# 5V_3V3_DIGITAL.net
KiCad netlist of a schematic drawn in Altium Designer
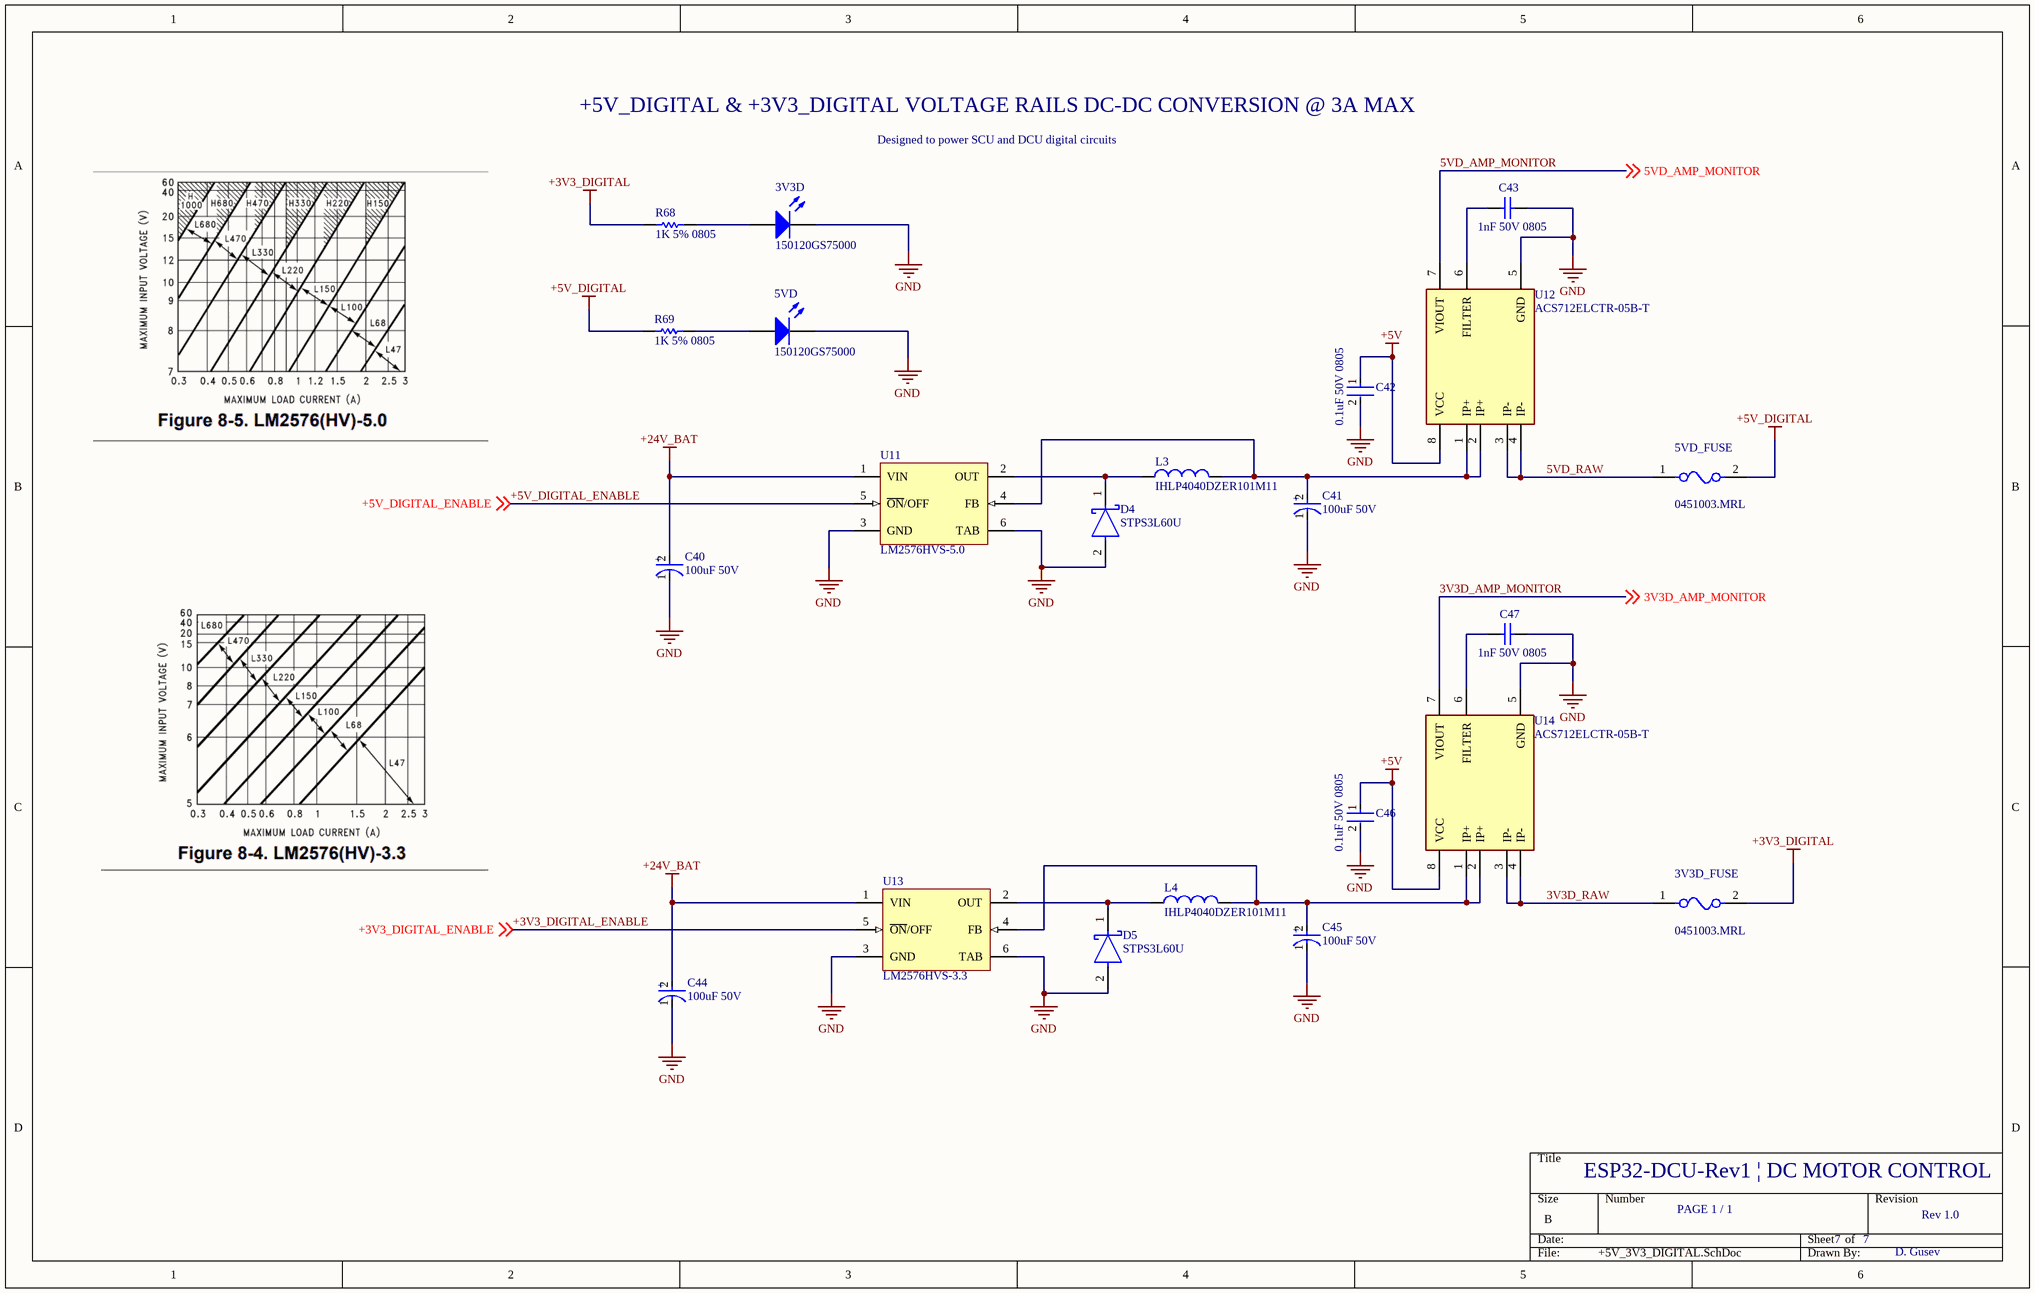
[diagram p0: +5V_3V3_DIGITAL.SchDoc]

(export (version "E")
  (design (tool "Eeschema 10.0.6"))
  (components
    (comp (ref "3V3D")
      (value "150120GS75000")
      (footprint "1206_A")
      (description "SMD mono-color Chip LED, WL-SMCW, Green")
      (fields (field (name "MANUFACTURER") "Wuerth Elektronik"))
      (libsource (lib "Altium Content Vault") (part "WE-LED_K1A2-2"))
    )
    (comp (ref "3V3D_FUSE")
      (value "0451003.MRL")
      (footprint "FP-0451-MFG")
      (description "FUSE BRD MNT 3A 125VAC/VDC 2SMD")
      (fields
        (field (name "MANUFACTURER") "Littelfuse Inc")
        (field (name "OCTOPART") "https://octopart.com/0451003.mrl-littelfuse-566380")
      )
      (libsource (lib "Altium Content Vault") (part "5bcf9b9f640e542cf0359d10258e979"))
    )
    (comp (ref "5VD")
      (value "150120GS75000")
      (footprint "1206_A")
      (description "SMD mono-color Chip LED, WL-SMCW, Green")
      (fields (field (name "MANUFACTURER") "Wuerth Elektronik"))
      (libsource (lib "Altium Content Vault") (part "WE-LED_K1A2-2"))
    )
    (comp (ref "5VD_FUSE")
      (value "0451003.MRL")
      (footprint "FP-0451-MFG")
      (description "FUSE BRD MNT 3A 125VAC/VDC 2SMD")
      (fields
        (field (name "MANUFACTURER") "Littelfuse Inc")
        (field (name "OCTOPART") "https://octopart.com/0451003.mrl-littelfuse-566380")
      )
      (libsource (lib "Altium Content Vault") (part "5bcf9b9f640e542cf0359d10258e979"))
    )
    (comp (ref "C40")
      (value "100uF 50V")
      (footprint "FP-EEE-FK1H101P-MFG")
      (description "CAP ALUM 100UF 20% 50V SMD")
      (fields (field (name "TOLERANCE") "20%") (field (name "MANUFACTURER PART NUMBER") "EEE-FK1H101P"))
      (libsource (lib "Altium Content Vault") (part "cf48714ba7e38822c1575c7ec0b6d1f"))
    )
    (comp (ref "C41")
      (value "100uF 50V")
      (footprint "FP-EEE-FK1H101P-MFG")
      (description "CAP ALUM 100UF 20% 50V SMD")
      (fields (field (name "TOLERANCE") "20%") (field (name "MANUFACTURER PART NUMBER") "EEE-FK1H101P"))
      (libsource (lib "Altium Content Vault") (part "cf48714ba7e38822c1575c7ec0b6d1f"))
    )
    (comp (ref "C42")
      (value "0.1uF 50V 0805")
      (footprint "FP-C0805C-DN-MFG")
      (description "CAP CER 0.1UF 50V X7R 0805")
      (fields
        (field (name "MANUFACTURER PART NUMBER") "C0805C104K5RACTU")
        (field (name "MANUFACTURER") "KEMET")
      )
      (libsource (lib "Altium Content Vault") (part "b4654b650e69147ec39a6b967a45e02"))
    )
    (comp (ref "C43")
      (value "1nF 50V 0805")
      (footprint "CAPC2013X94X50ML20T25")
      (fields
        (field (name "PART NUMBER") "08055C102KAT2A.")
        (field (name "MANUFACTURER") "AVX Interconnect / Elco")
      )
      (libsource (lib "Altium Content Vault") (part "CAP"))
    )
    (comp (ref "C44")
      (value "100uF 50V")
      (footprint "FP-EEE-FK1H101P-MFG")
      (description "CAP ALUM 100UF 20% 50V SMD")
      (fields (field (name "TOLERANCE") "20%") (field (name "MANUFACTURER PART NUMBER") "EEE-FK1H101P"))
      (libsource (lib "Altium Content Vault") (part "cf48714ba7e38822c1575c7ec0b6d1f"))
    )
    (comp (ref "C45")
      (value "100uF 50V")
      (footprint "FP-EEE-FK1H101P-MFG")
      (description "CAP ALUM 100UF 20% 50V SMD")
      (fields (field (name "TOLERANCE") "20%") (field (name "MANUFACTURER PART NUMBER") "EEE-FK1H101P"))
      (libsource (lib "Altium Content Vault") (part "cf48714ba7e38822c1575c7ec0b6d1f"))
    )
    (comp (ref "C46")
      (value "0.1uF 50V 0805")
      (footprint "FP-C0805C-DN-MFG")
      (description "CAP CER 0.1UF 50V X7R 0805")
      (fields
        (field (name "MANUFACTURER PART NUMBER") "C0805C104K5RACTU")
        (field (name "MANUFACTURER") "KEMET")
      )
      (libsource (lib "Altium Content Vault") (part "b4654b650e69147ec39a6b967a45e02"))
    )
    (comp (ref "C47")
      (value "1nF 50V 0805")
      (footprint "CAPC2013X94X50ML20T25")
      (fields
        (field (name "PART NUMBER") "08055C102KAT2A.")
        (field (name "MANUFACTURER") "AVX Interconnect / Elco")
      )
      (libsource (lib "Altium Content Vault") (part "CAP"))
    )
    (comp (ref "D4")
      (value "STPS3L60U")
      (footprint "FP-SMB-MFG")
      (description "DIODE SCHOTTKY 60V 3A SMB")
      (fields
        (field (name "OCTOPART") "https://octopart.com/stps3l60u-stmicroelectronics-334329")
        (field (name "MANUFACTURER") "STMicroelectronics")
      )
      (libsource (lib "Altium Content Vault") (part "fefb30dabb5d097ae2f038500735429"))
    )
    (comp (ref "D5")
      (value "STPS3L60U")
      (footprint "FP-SMB-MFG")
      (description "DIODE SCHOTTKY 60V 3A SMB")
      (fields
        (field (name "OCTOPART") "https://octopart.com/stps3l60u-stmicroelectronics-334329")
        (field (name "MANUFACTURER") "STMicroelectronics")
      )
      (libsource (lib "Altium Content Vault") (part "fefb30dabb5d097ae2f038500735429"))
    )
    (comp (ref "L3")
      (value "IHLP4040DZER101M11")
      (footprint "VISH-IHLP4040DZER101M11_V")
      (fields (field (name "MANUFACTURER") "Vishay") (field (name "TOLERANCE") "20%"))
      (libsource (lib "Altium Content Vault") (part "IND-2"))
    )
    (comp (ref "L4")
      (value "IHLP4040DZER101M11")
      (footprint "VISH-IHLP4040DZER101M11_V")
      (fields (field (name "MANUFACTURER") "Vishay") (field (name "TOLERANCE") "20%"))
      (libsource (lib "") (part "IND-2_1"))
    )
    (comp (ref "R68")
      (value "1K 5% 0805")
      (footprint "RESC2013X60X40ML20T25")
      (fields (field (name "PART NUMBER") "ERA6AEB123V") (field (name "MANUFACTURER") "Panasonic"))
      (libsource (lib "Altium Content Vault") (part "RES"))
    )
    (comp (ref "R69")
      (value "1K 5% 0805")
      (footprint "RESC2013X60X40ML20T25")
      (fields (field (name "PART NUMBER") "ERA6AEB123V") (field (name "MANUFACTURER") "Panasonic"))
      (libsource (lib "Altium Content Vault") (part "RES"))
    )
    (comp (ref "U11")
      (value "LM2576HVS-5.0")
      (footprint "KTT0005B_L")
      (description "SIMPLE SWITCHER® 3A Step-Down Voltage Regulator, 5-pin TO-263")
      (fields (field (name "MANUFACTURER") "Texas Instruments"))
      (libsource (lib "Altium Content Vault") (part "PM-REG-LM2575HVS-12"))
    )
    (comp (ref "U12")
      (value "ACS712ELCTR-05B-T")
      (footprint "FP-LC-8-IPC_A")
      (description "SENSOR CURRENT HALL 5A AC/DC")
      (fields (field (name "VOLTAGE") "5V"))
      (libsource (lib "Altium Content Vault") (part "160a4736de78720bdb7fdad13a6f0ac"))
    )
    (comp (ref "U13")
      (value "LM2576HVS-3.3")
      (footprint "KTT0005B_M")
      (description "SIMPLE SWITCHER® 3A Step-Down Voltage Regulator, 5-pin TO-263")
      (fields (field (name "MANUFACTURER") "Texas Instruments"))
      (libsource (lib "Altium Content Vault") (part "PM-REG-LM2575HVS-12"))
    )
    (comp (ref "U14")
      (value "ACS712ELCTR-05B-T")
      (footprint "FP-LC-8-IPC_A")
      (description "SENSOR CURRENT HALL 5A AC/DC")
      (fields (field (name "VOLTAGE") "5V"))
      (libsource (lib "Altium Content Vault") (part "160a4736de78720bdb7fdad13a6f0ac"))
    )
  )
  (nets
    (net (code "1") (name "+3V3_DIGITAL") (class "Default")
      (node (ref "3V3D_FUSE") (pin "2") (pinfunction "2_2") (pintype "passive"))
      (node (ref "R68") (pin "2") (pinfunction "2_2") (pintype "passive"))
    )
    (net (code "2") (name "+3V3_DIGITAL_ENABLE") (class "Default")
      (node (ref "U13") (pin "5") (pinfunction "~{ON}/OFF_5") (pintype "input"))
    )
    (net (code "3") (name "+5V") (class "Default")
      (node (ref "C42") (pin "1") (pinfunction "1_1") (pintype "passive"))
      (node (ref "C46") (pin "1") (pinfunction "1_1") (pintype "passive"))
      (node (ref "U12") (pin "8") (pinfunction "VCC_8") (pintype "power_in"))
      (node (ref "U14") (pin "8") (pinfunction "VCC_8") (pintype "power_in"))
    )
    (net (code "4") (name "+5V_DIGITAL") (class "Default")
      (node (ref "5VD_FUSE") (pin "2") (pinfunction "2_2") (pintype "passive"))
      (node (ref "R69") (pin "2") (pinfunction "2_2") (pintype "passive"))
    )
    (net (code "5") (name "+5V_DIGITAL_ENABLE") (class "Default")
      (node (ref "U11") (pin "5") (pinfunction "~{ON}/OFF_5") (pintype "input"))
    )
    (net (code "6") (name "+24V_BAT") (class "Default")
      (node (ref "C40") (pin "2") (pinfunction "A_2") (pintype "passive"))
      (node (ref "C44") (pin "2") (pinfunction "A_2") (pintype "passive"))
      (node (ref "U11") (pin "1") (pinfunction "VIN_1") (pintype "power_in"))
      (node (ref "U13") (pin "1") (pinfunction "VIN_1") (pintype "power_in"))
    )
    (net (code "7") (name "/3V3D_RAW") (class "Default")
      (node (ref "3V3D_FUSE") (pin "1") (pinfunction "1_1") (pintype "passive"))
      (node (ref "U14") (pin "3") (pinfunction "IP-_3") (pintype "passive"))
      (node (ref "U14") (pin "4") (pinfunction "IP-_4") (pintype "passive"))
    )
    (net (code "8") (name "/5VD_RAW") (class "Default")
      (node (ref "5VD_FUSE") (pin "1") (pinfunction "1_1") (pintype "passive"))
      (node (ref "U12") (pin "3") (pinfunction "IP-_3") (pintype "passive"))
      (node (ref "U12") (pin "4") (pinfunction "IP-_4") (pintype "passive"))
    )
    (net (code "9") (name "3V3D_AMP_MONITOR") (class "Default")
      (node (ref "U14") (pin "7") (pinfunction "VIOUT_7") (pintype "passive"))
    )
    (net (code "10") (name "5VD_AMP_MONITOR") (class "Default")
      (node (ref "U12") (pin "7") (pinfunction "VIOUT_7") (pintype "passive"))
    )
    (net (code "11") (name "GND") (class "Default")
      (node (ref "3V3D") (pin "1") (pinfunction "K_1") (pintype "passive"))
      (node (ref "5VD") (pin "1") (pinfunction "K_1") (pintype "passive"))
      (node (ref "C40") (pin "1") (pinfunction "C_1") (pintype "passive"))
      (node (ref "C41") (pin "1") (pinfunction "C_1") (pintype "passive"))
      (node (ref "C42") (pin "2") (pinfunction "2_2") (pintype "passive"))
      (node (ref "C43") (pin "2") (pinfunction "2_2") (pintype "passive"))
      (node (ref "C44") (pin "1") (pinfunction "C_1") (pintype "passive"))
      (node (ref "C45") (pin "1") (pinfunction "C_1") (pintype "passive"))
      (node (ref "C46") (pin "2") (pinfunction "2_2") (pintype "passive"))
      (node (ref "C47") (pin "2") (pinfunction "2_2") (pintype "passive"))
      (node (ref "D4") (pin "2") (pinfunction "A_2") (pintype "passive"))
      (node (ref "D5") (pin "2") (pinfunction "A_2") (pintype "passive"))
      (node (ref "U11") (pin "3") (pinfunction "GND_3") (pintype "power_in"))
      (node (ref "U11") (pin "6") (pinfunction "TAB_6") (pintype "power_in"))
      (node (ref "U12") (pin "5") (pinfunction "GND_5") (pintype "power_in"))
      (node (ref "U13") (pin "3") (pinfunction "GND_3") (pintype "power_in"))
      (node (ref "U13") (pin "6") (pinfunction "TAB_6") (pintype "power_in"))
      (node (ref "U14") (pin "5") (pinfunction "GND_5") (pintype "power_in"))
    )
    (net (code "12") (name "Net-(3V3D-A)") (class "Default")
      (node (ref "3V3D") (pin "2") (pinfunction "A_2") (pintype "passive"))
      (node (ref "R68") (pin "1") (pinfunction "1_1") (pintype "passive"))
    )
    (net (code "13") (name "Net-(5VD-A)") (class "Default")
      (node (ref "5VD") (pin "2") (pinfunction "A_2") (pintype "passive"))
      (node (ref "R69") (pin "1") (pinfunction "1_1") (pintype "passive"))
    )
    (net (code "14") (name "Net-(C41-A)") (class "Default")
      (node (ref "C41") (pin "2") (pinfunction "A_2") (pintype "passive"))
      (node (ref "L3") (pin "2") (pinfunction "2_2") (pintype "passive"))
      (node (ref "U11") (pin "4") (pinfunction "FB_4") (pintype "input"))
      (node (ref "U12") (pin "1") (pinfunction "IP+_1") (pintype "passive"))
      (node (ref "U12") (pin "2") (pinfunction "IP+_2") (pintype "passive"))
    )
    (net (code "15") (name "Net-(C45-A)") (class "Default")
      (node (ref "C45") (pin "2") (pinfunction "A_2") (pintype "passive"))
      (node (ref "L4") (pin "1") (pinfunction "1_1") (pintype "passive"))
      (node (ref "U13") (pin "4") (pinfunction "FB_4") (pintype "input"))
      (node (ref "U14") (pin "1") (pinfunction "IP+_1") (pintype "passive"))
      (node (ref "U14") (pin "2") (pinfunction "IP+_2") (pintype "passive"))
    )
    (net (code "16") (name "Net-(D4-K)") (class "Default")
      (node (ref "D4") (pin "1") (pinfunction "K_1") (pintype "passive"))
      (node (ref "L3") (pin "1") (pinfunction "1_1") (pintype "passive"))
      (node (ref "U11") (pin "2") (pinfunction "OUT_2") (pintype "power_in"))
    )
    (net (code "17") (name "Net-(D5-K)") (class "Default")
      (node (ref "D5") (pin "1") (pinfunction "K_1") (pintype "passive"))
      (node (ref "L4") (pin "2") (pinfunction "2_2") (pintype "passive"))
      (node (ref "U13") (pin "2") (pinfunction "OUT_2") (pintype "power_in"))
    )
    (net (code "18") (name "Net-(U12-FILTER)") (class "Default")
      (node (ref "C43") (pin "1") (pinfunction "1_1") (pintype "passive"))
      (node (ref "U12") (pin "6") (pinfunction "FILTER_6") (pintype "passive"))
    )
    (net (code "19") (name "Net-(U14-FILTER)") (class "Default")
      (node (ref "C47") (pin "1") (pinfunction "1_1") (pintype "passive"))
      (node (ref "U14") (pin "6") (pinfunction "FILTER_6") (pintype "passive"))
    )
  )
)
